# Principal_v1.net
KiCad netlist of a schematic drawn in Altium Designer
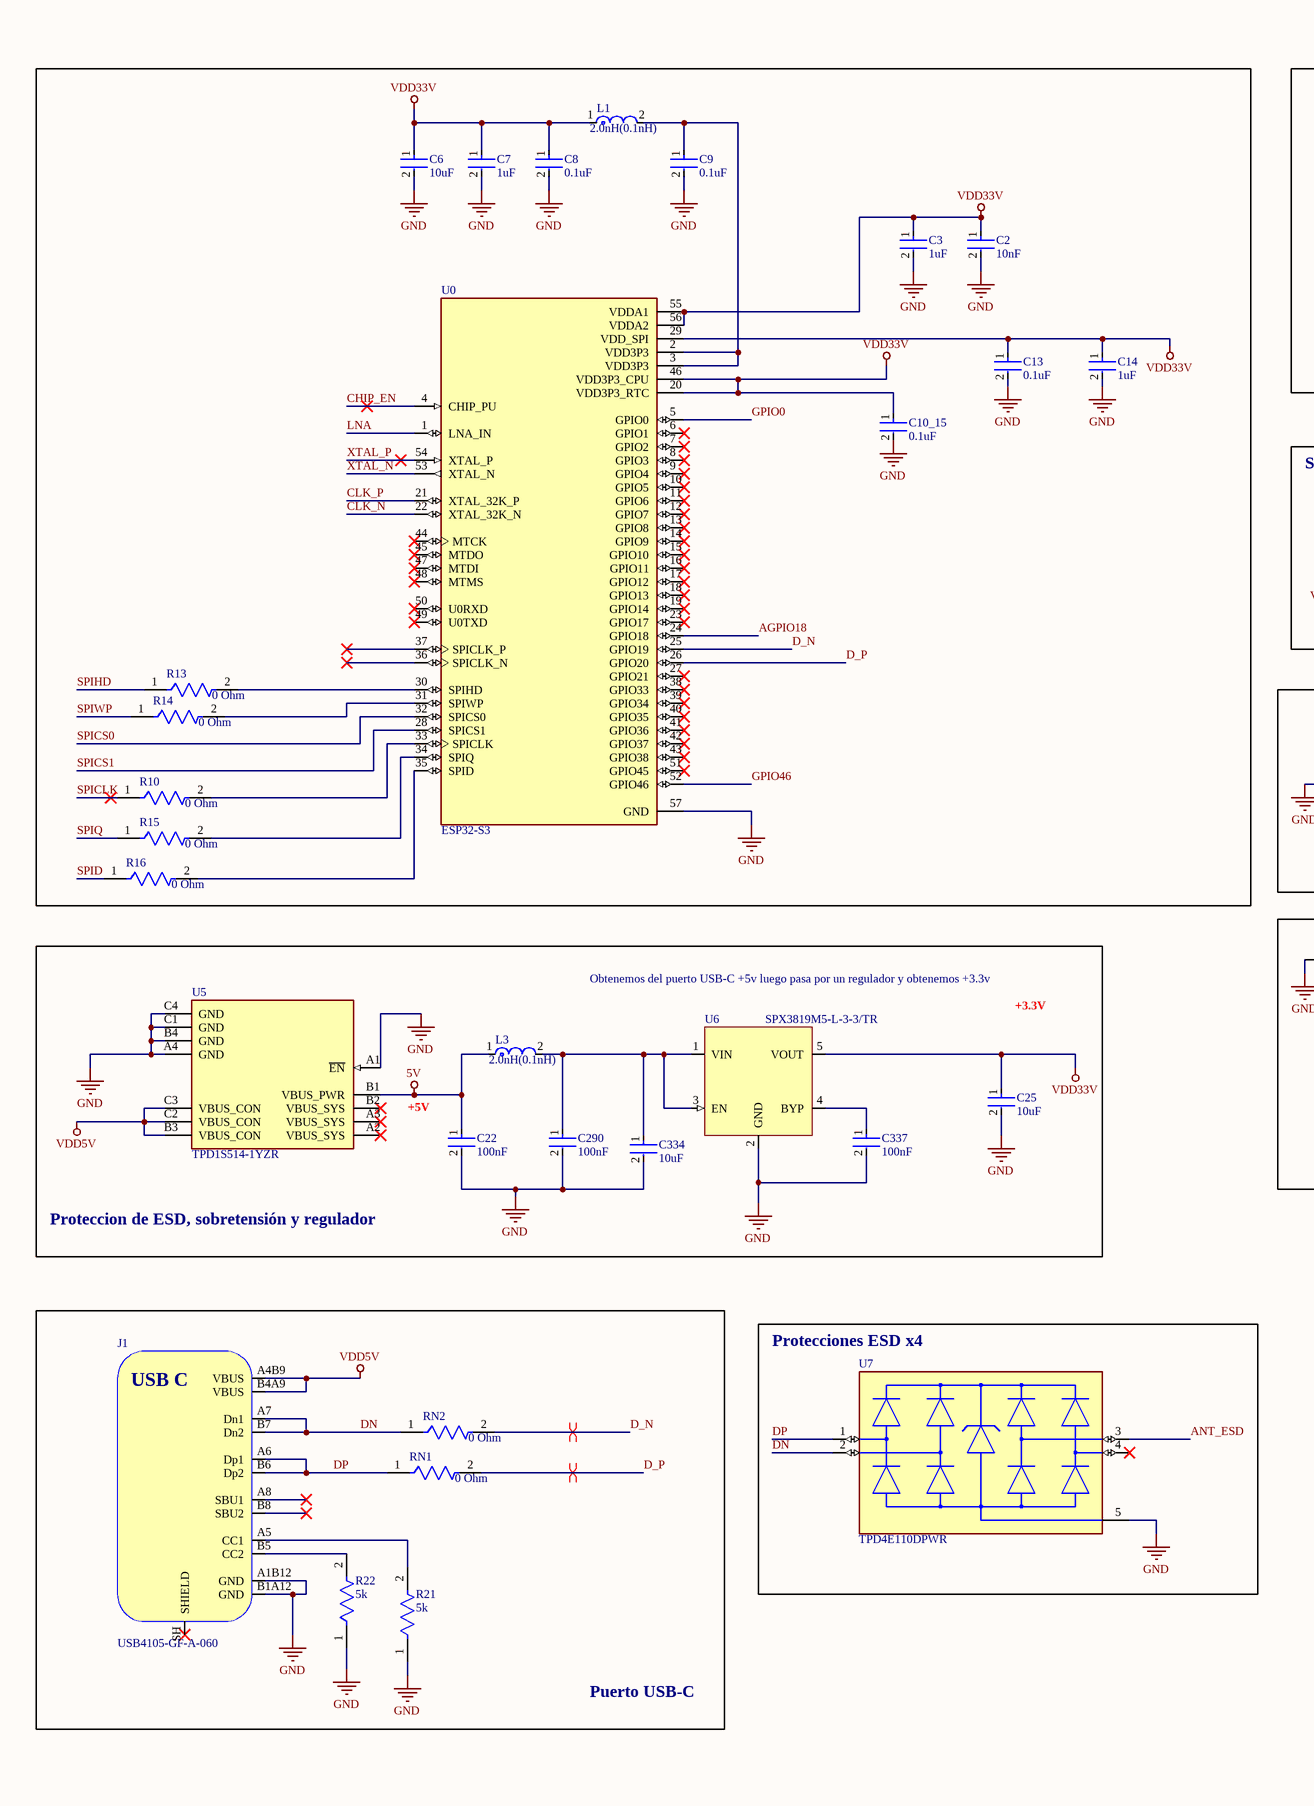
[diagram p0: Principal_v1.SchDoc, left]
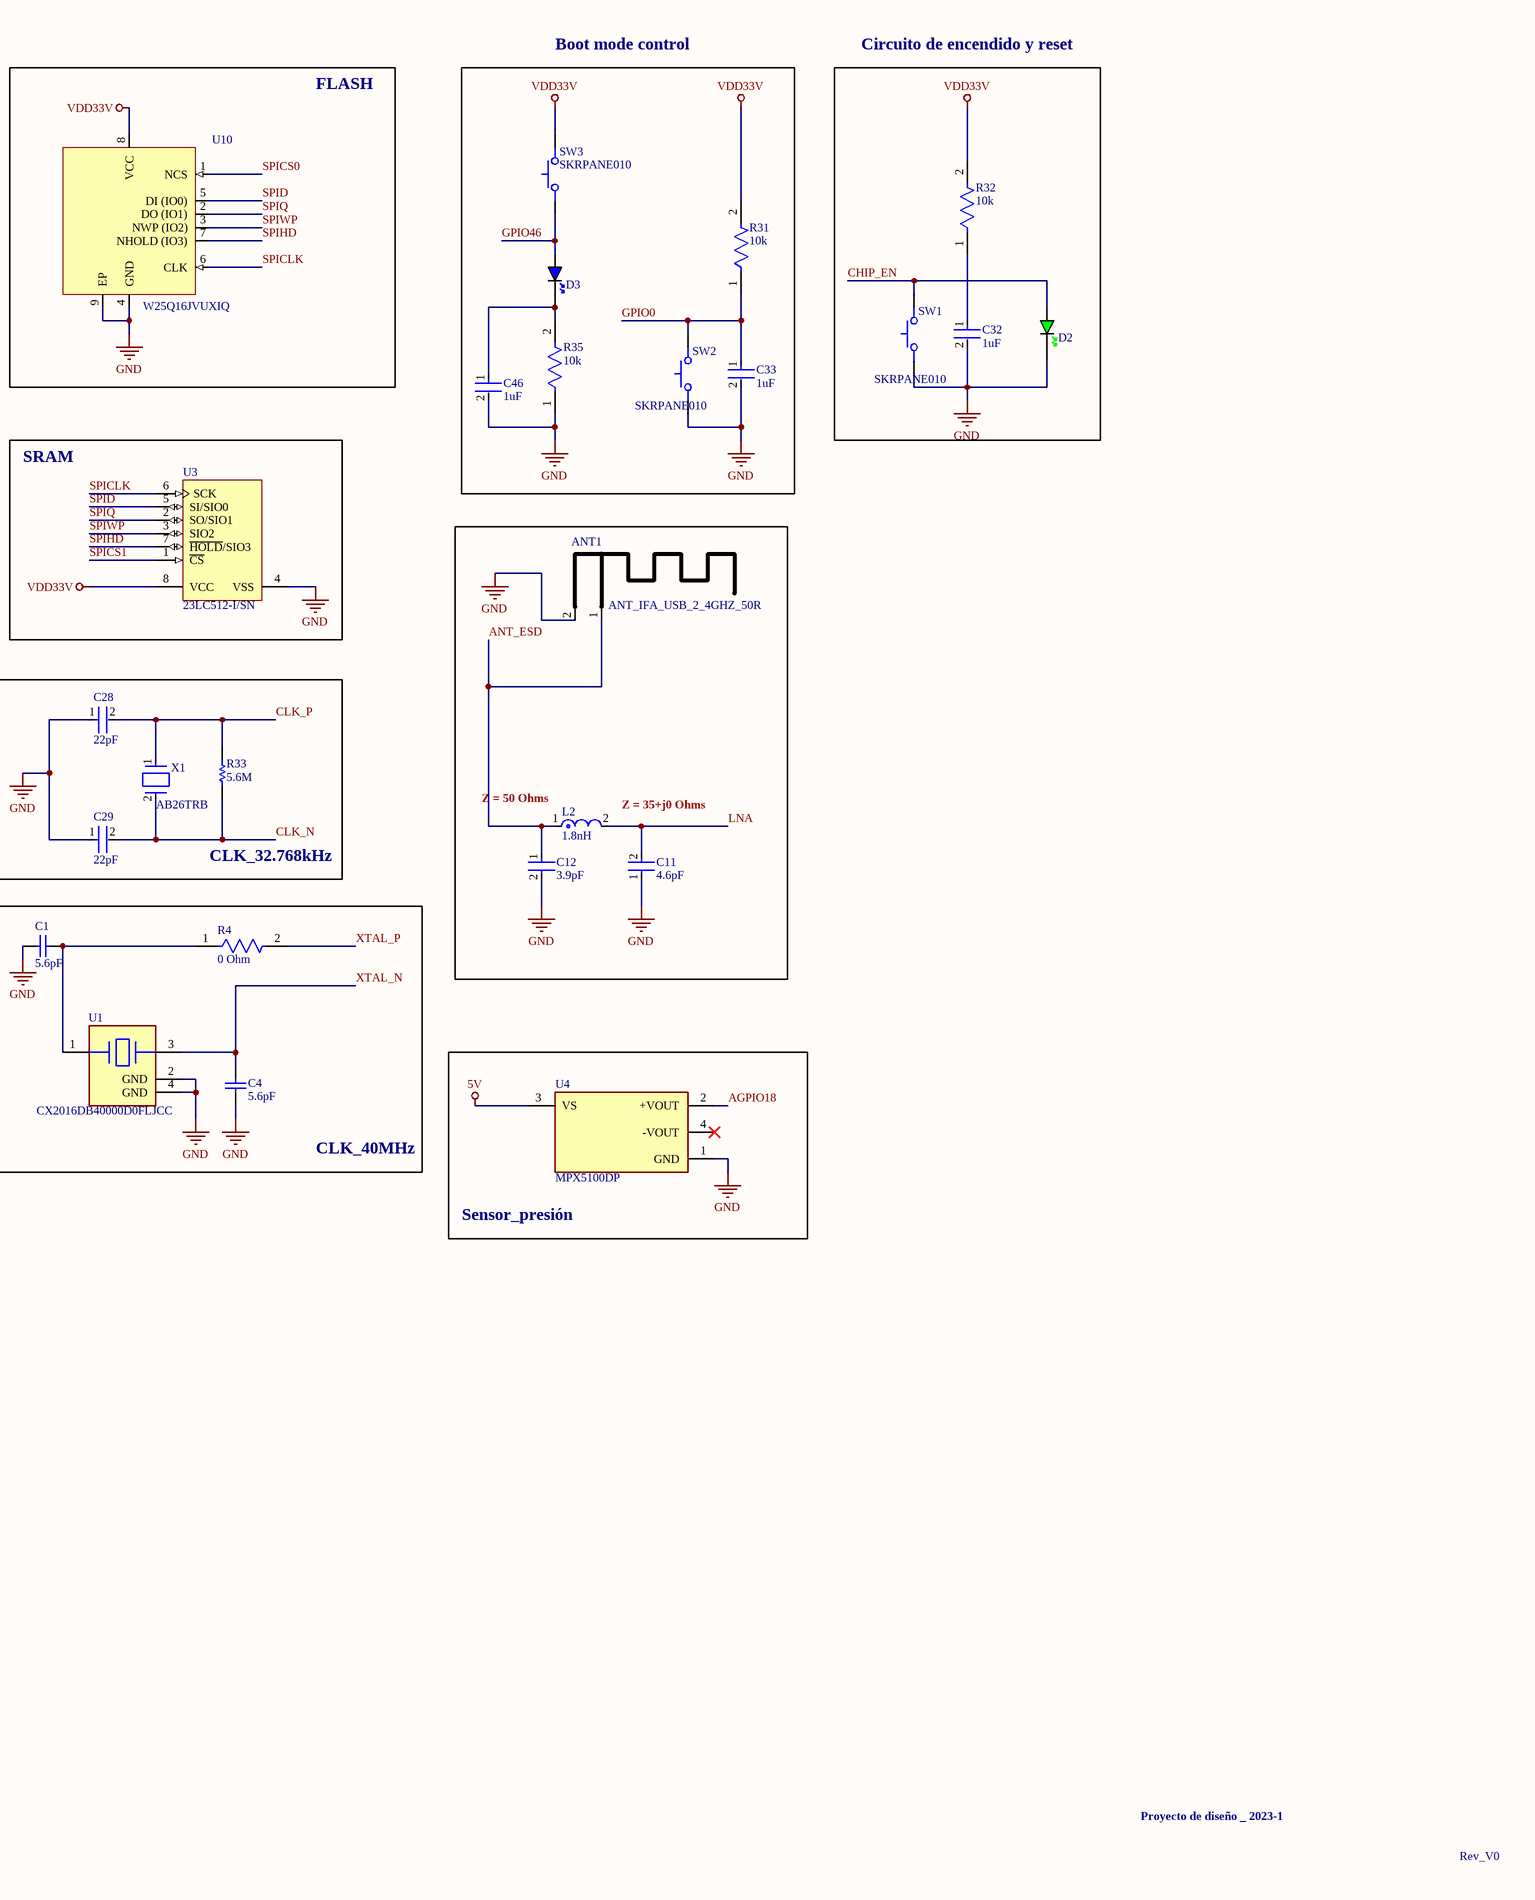
[diagram p1: Principal_v1.SchDoc, right]

(export (version "E")
  (design (tool "Eeschema 10.0.6"))
  (components
    (comp (ref "ANT1")
      (value "ANT_IFA_USB_2_4GHZ_50R")
      (footprint "ANT_IFA_USB_2_4GHZ_50R")
      (description "Inverted F 2.4GHz ISM PCB Antenna 50 Ohm")
      (fields (field (name "SOURCE") "Schematic-Lib-PhilsLab.SchLib"))
      (libsource (lib "Universidad Industrial de Santander") (part "ANT_IFA_USB_2_4GHZ_50R"))
    )
    (comp (ref "C1")
      (value "5.6pF")
      (footprint "CAPC1006X50X20LL10T10")
      (fields
        (field (name "MANUFACTURER") "AVX Interconnect / Elco")
        (field (name "PART NUMBER") "04023J5R6BBSTR")
      )
      (libsource (lib "Altium Content Vault") (part "CAP"))
    )
    (comp (ref "C2")
      (value "10nF")
      (footprint "FP-GRM033-0_03-IPC_B")
      (description "Chip Multilayer Ceramic Capacitors for General Purpose, 0201, 10000pF, X7R, 15%, 10%, 10V")
      (fields (field (name "VOLTAGE") "10V") (field (name "TOLERANCE") "10%"))
      (libsource (lib "Altium Content Vault") (part "b4654b650e69147ec39a6b967a45e02"))
    )
    (comp (ref "C3")
      (value "1uF")
      (footprint "FP-C0402C105K9PACTU-MFG")
      (description "CAP CER 1UF 6.3V X5R 0402")
      (fields (field (name "TOLERANCE") "10%") (field (name "VOLTAGE") "6.3V"))
      (libsource (lib "Altium Content Vault") (part "11868f565c42a9108669ba33697ecf6"))
    )
    (comp (ref "C4")
      (value "5.6pF")
      (footprint "CAPC1006X50X20LL10T10")
      (fields
        (field (name "MANUFACTURER") "AVX Interconnect / Elco")
        (field (name "PART NUMBER") "04023J5R6BBSTR")
      )
      (libsource (lib "Altium Content Vault") (part "CAP"))
    )
    (comp (ref "C6")
      (value "10uF")
      (footprint "FP-GRM155-0_2-IPC_C")
      (description "Chip Multilayer Ceramic Capacitors for General Purpose, 0402, 10uF, X5R, 15%, 20%, 6.3V")
      (libsource (lib "Altium Content Vault") (part "b4654b650e69147ec39a6b967a45e02"))
    )
    (comp (ref "C7")
      (value "1uF")
      (footprint "FP-C0402C105K9PACTU-MFG")
      (description "CAP CER 1UF 6.3V X5R 0402")
      (fields (field (name "TOLERANCE") "10%") (field (name "VOLTAGE") "6.3V"))
      (libsource (lib "Altium Content Vault") (part "11868f565c42a9108669ba33697ecf6"))
    )
    (comp (ref "C8")
      (value "0.1uF")
      (footprint "FP-CL278-IPC_C")
      (description "Cap Ceramic 100nF 25V X5R ±10% SMD 0402 +85°C Paper T/R")
      (fields (field (name "VOLTAGE") "25V") (field (name "TOLERANCE") "10%"))
      (libsource (lib "Altium Content Vault") (part "b4654b650e69147ec39a6b967a45e02"))
    )
    (comp (ref "C9")
      (value "0.1uF")
      (footprint "FP-CL278-IPC_C")
      (description "Cap Ceramic 100nF 25V X5R ±10% SMD 0402 +85°C Paper T/R")
      (fields (field (name "VOLTAGE") "25V") (field (name "TOLERANCE") "10%"))
      (libsource (lib "Altium Content Vault") (part "b4654b650e69147ec39a6b967a45e02"))
    )
    (comp (ref "C10_15")
      (value "0.1uF")
      (footprint "FP-CL278-IPC_C")
      (description "Cap Ceramic 100nF 25V X5R ±10% SMD 0402 +85°C Paper T/R")
      (fields (field (name "VOLTAGE") "25V") (field (name "TOLERANCE") "10%"))
      (libsource (lib "Altium Content Vault") (part "b4654b650e69147ec39a6b967a45e02"))
    )
    (comp (ref "C11")
      (value "4.6pF")
      (footprint "FP-CBR04C-MFG")
      (description "CBR0402 4.6 pF 30ppm/°C 0.1 pF C0G 50 V")
      (fields (field (name "MANUFACTURER PART NUMBER") "CBR04C469B5GAC") (field (name "TOLERANCE") "0.1 pF"))
      (libsource (lib "Altium Content Vault") (part "236180d848d6139a670b325ea6854c9"))
    )
    (comp (ref "C12")
      (value "3.9pF")
      (footprint "FP-GRM033-0_03-IPC_B")
      (description "Chip Multilayer Ceramic Capacitors for General Purpose, 0201, 3.9pF, C0G, 30ppm/°C, 0.25pF, 50V")
      (libsource (lib "Altium Content Vault") (part "b4654b650e69147ec39a6b967a45e02"))
    )
    (comp (ref "C13")
      (value "0.1uF")
      (footprint "FP-CL278-IPC_C")
      (description "Cap Ceramic 100nF 25V X5R ±10% SMD 0402 +85°C Paper T/R")
      (fields (field (name "VOLTAGE") "25V") (field (name "TOLERANCE") "10%"))
      (libsource (lib "Altium Content Vault") (part "b4654b650e69147ec39a6b967a45e02"))
    )
    (comp (ref "C14")
      (value "1uF")
      (footprint "FP-C0402C105K9PACTU-MFG")
      (description "CAP CER 1UF 6.3V X5R 0402")
      (fields (field (name "TOLERANCE") "10%") (field (name "VOLTAGE") "6.3V"))
      (libsource (lib "Altium Content Vault") (part "11868f565c42a9108669ba33697ecf6"))
    )
    (comp (ref "C22")
      (value "100nF")
      (footprint "FP-CL278-IPC_C")
      (description "Cap Ceramic 100nF 25V X5R ±10% SMD 0402 +85°C Paper T/R")
      (fields (field (name "VOLTAGE") "25V") (field (name "TOLERANCE") "10%"))
      (libsource (lib "Altium Content Vault") (part "b4654b650e69147ec39a6b967a45e02"))
    )
    (comp (ref "C25")
      (value "10uF")
      (footprint "FP-GRM155-0_2-IPC_C")
      (description "Chip Multilayer Ceramic Capacitors for General Purpose, 0402, 10uF, X5R, 15%, 20%, 6.3V")
      (libsource (lib "Altium Content Vault") (part "b4654b650e69147ec39a6b967a45e02"))
    )
    (comp (ref "C28")
      (value "22pF")
      (footprint "FP-C0603C-CF-MFG")
      (description "Cap Ceramic 22pF 50V C0G 5% SMD 0603 125°C Paper T/R")
      (fields (field (name "MANUFACTURER PART NUMBER") "C0603C220J5GACTU") (field (name "TOLERANCE") "0.05"))
      (libsource (lib "Altium Content Vault") (part "b4654b650e69147ec39a6b967a45e02"))
    )
    (comp (ref "C29")
      (value "22pF")
      (footprint "FP-C0603C-CF-MFG")
      (description "Cap Ceramic 22pF 50V C0G 5% SMD 0603 125°C Paper T/R")
      (fields (field (name "MANUFACTURER PART NUMBER") "C0603C220J5GACTU") (field (name "TOLERANCE") "0.05"))
      (libsource (lib "Altium Content Vault") (part "b4654b650e69147ec39a6b967a45e02"))
    )
    (comp (ref "C32")
      (value "1uF")
      (footprint "FP-C0402C105K9PACTU-MFG")
      (description "CAP CER 1UF 6.3V X5R 0402")
      (fields (field (name "TOLERANCE") "10%") (field (name "VOLTAGE") "6.3V"))
      (libsource (lib "Altium Content Vault") (part "11868f565c42a9108669ba33697ecf6"))
    )
    (comp (ref "C33")
      (value "1uF")
      (footprint "FP-C0402C105K9PACTU-MFG")
      (description "CAP CER 1UF 6.3V X5R 0402")
      (fields (field (name "TOLERANCE") "10%") (field (name "VOLTAGE") "6.3V"))
      (libsource (lib "Altium Content Vault") (part "11868f565c42a9108669ba33697ecf6"))
    )
    (comp (ref "C46")
      (value "1uF")
      (footprint "FP-C0402C105K9PACTU-MFG")
      (description "CAP CER 1UF 6.3V X5R 0402")
      (fields (field (name "TOLERANCE") "10%") (field (name "VOLTAGE") "6.3V"))
      (libsource (lib "Altium Content Vault") (part "11868f565c42a9108669ba33697ecf6"))
    )
    (comp (ref "C290")
      (value "100nF")
      (footprint "FP-CL278-IPC_C")
      (description "Cap Ceramic 100nF 25V X5R ±10% SMD 0402 +85°C Paper T/R")
      (fields (field (name "VOLTAGE") "25V") (field (name "TOLERANCE") "10%"))
      (libsource (lib "Altium Content Vault") (part "b4654b650e69147ec39a6b967a45e02"))
    )
    (comp (ref "C334")
      (value "10uF")
      (footprint "FP-GRM155-0_2-IPC_C")
      (description "Chip Multilayer Ceramic Capacitors for General Purpose, 0402, 10uF, X5R, 15%, 20%, 6.3V")
      (libsource (lib "Altium Content Vault") (part "b4654b650e69147ec39a6b967a45e02"))
    )
    (comp (ref "C337")
      (value "100nF")
      (footprint "FP-CL278-IPC_C")
      (description "Cap Ceramic 100nF 25V X5R ±10% SMD 0402 +85°C Paper T/R")
      (fields (field (name "VOLTAGE") "25V") (field (name "TOLERANCE") "10%"))
      (libsource (lib "Altium Content Vault") (part "b4654b650e69147ec39a6b967a45e02"))
    )
    (comp (ref "D2")
      (value "GREEN")
      (footprint "LED_0603_GREEN")
      (description "LED 0603 GREEN SMD")
      (libsource (lib "Schematic-Lib-PhilsLab") (part "LED_0603_GREEN"))
    )
    (comp (ref "D3")
      (value "BLUE")
      (footprint "LED_0603_BLUE")
      (description "LED 0603 BLUE SMD")
      (libsource (lib "Schematic-Lib-PhilsLab") (part "LED_0603_BLUE"))
    )
    (comp (ref "J1")
      (value "USB4105-GF-A-060")
      (footprint "USB4105-GF-A-060")
      (description "USB Connector Type C SMT 12 Pin")
      (fields (field (name "MANUFACTURER") "GCT") (field (name "SOURCE") "Schematic-Lib-PhilsLab.SchLib"))
      (libsource (lib "Universidad Industrial de Santander") (part "USB4105-GF-A-060"))
    )
    (comp (ref "L1")
      (value "2.0nH(0.1nH)")
      (footprint "FP-LQG15HH_02-MFG")
      (description "Multilayer type RF Inductor 2nH ±0.1nH 0.09Ω 900mA 0402")
      (libsource (lib "Altium Content Vault") (part "4cc4b267dca4c8e51f7102f422741d8"))
    )
    (comp (ref "L2")
      (value "1.8nH")
      (footprint "FP-LQP03TG_02-IPC_B")
      (description "Film type RF Inductor 1.8nH ±0.1nH 600mA 0.15Ω 0201 (0603)")
      (libsource (lib "Altium Content Vault") (part "4cc4b267dca4c8e51f7102f422741d8"))
    )
    (comp (ref "L3")
      (value "2.0nH(0.1nH)")
      (footprint "FP-LQG15HH_02-MFG")
      (description "Multilayer type RF Inductor 2nH ±0.1nH 0.09Ω 900mA 0402")
      (libsource (lib "Altium Content Vault") (part "4cc4b267dca4c8e51f7102f422741d8"))
    )
    (comp (ref "R4")
      (value "0 Ohm")
      (footprint "FP-RMCF0402-MFG")
      (description "RES 0 OHM JUMPER 1/16W 0402")
      (libsource (lib "Altium Content Vault") (part "1029c3af85768c4190bb7ad29bc67b5"))
    )
    (comp (ref "R10")
      (value "0 Ohm")
      (footprint "FP-RMCF0402-MFG")
      (description "RES 0 OHM JUMPER 1/16W 0402")
      (libsource (lib "Altium Content Vault") (part "1029c3af85768c4190bb7ad29bc67b5"))
    )
    (comp (ref "R13")
      (value "0 Ohm")
      (footprint "FP-RMCF0402-MFG")
      (description "RES 0 OHM JUMPER 1/16W 0402")
      (libsource (lib "Altium Content Vault") (part "1029c3af85768c4190bb7ad29bc67b5"))
    )
    (comp (ref "R14")
      (value "0 Ohm")
      (footprint "FP-RMCF0402-MFG")
      (description "RES 0 OHM JUMPER 1/16W 0402")
      (libsource (lib "Altium Content Vault") (part "1029c3af85768c4190bb7ad29bc67b5"))
    )
    (comp (ref "R15")
      (value "0 Ohm")
      (footprint "FP-RMCF0402-MFG")
      (description "RES 0 OHM JUMPER 1/16W 0402")
      (libsource (lib "Altium Content Vault") (part "1029c3af85768c4190bb7ad29bc67b5"))
    )
    (comp (ref "R16")
      (value "0 Ohm")
      (footprint "FP-RMCF0402-MFG")
      (description "RES 0 OHM JUMPER 1/16W 0402")
      (libsource (lib "Altium Content Vault") (part "1029c3af85768c4190bb7ad29bc67b5"))
    )
    (comp (ref "R21")
      (value "5k")
      (footprint "FP-PNM0402-IPC_C")
      (description "RES SMD 5K OHM 0.1% 1/20W 0402")
      (fields (field (name "TOLERANCE") "0.1%"))
      (libsource (lib "Altium Content Vault") (part "1029c3af85768c4190bb7ad29bc67b5"))
    )
    (comp (ref "R22")
      (value "5k")
      (footprint "FP-PNM0402-IPC_C")
      (description "RES SMD 5K OHM 0.1% 1/20W 0402")
      (fields (field (name "TOLERANCE") "0.1%"))
      (libsource (lib "Altium Content Vault") (part "1029c3af85768c4190bb7ad29bc67b5"))
    )
    (comp (ref "R31")
      (value "10k")
      (footprint "FP-CRGP0603-IPC_C")
      (description "CRGP 0603 10K 1%")
      (fields
        (field (name "OCTOPART") "https://octopart.com/crgp0603f10k-te+connectivity-91018721")
        (field (name "MANUFACTURER PART NUMBER") "CRGP0603F10K")
      )
      (libsource (lib "Altium Content Vault") (part "1029c3af85768c4190bb7ad29bc67b5"))
    )
    (comp (ref "R32")
      (value "10k")
      (footprint "FP-CRGP0603-IPC_C")
      (description "CRGP 0603 10K 1%")
      (fields
        (field (name "OCTOPART") "https://octopart.com/crgp0603f10k-te+connectivity-91018721")
        (field (name "MANUFACTURER PART NUMBER") "CRGP0603F10K")
      )
      (libsource (lib "Altium Content Vault") (part "1029c3af85768c4190bb7ad29bc67b5"))
    )
    (comp (ref "R33")
      (value "5.6M")
      (footprint "RESC1005X40X25ML05T10")
      (fields (field (name "MANUFACTURER") "Yageo / Phycomp") (field (name "PART NUMBER") "RC0402JR-075M6L"))
      (libsource (lib "Altium Content Vault") (part "RES"))
    )
    (comp (ref "R35")
      (value "10k")
      (footprint "FP-CRGP0603-IPC_C")
      (description "CRGP 0603 10K 1%")
      (fields
        (field (name "OCTOPART") "https://octopart.com/crgp0603f10k-te+connectivity-91018721")
        (field (name "MANUFACTURER PART NUMBER") "CRGP0603F10K")
      )
      (libsource (lib "Altium Content Vault") (part "1029c3af85768c4190bb7ad29bc67b5"))
    )
    (comp (ref "RN1")
      (value "0 Ohm")
      (footprint "FP-RMCF0402-MFG")
      (description "RES 0 OHM JUMPER 1/16W 0402")
      (libsource (lib "Altium Content Vault") (part "1029c3af85768c4190bb7ad29bc67b5"))
    )
    (comp (ref "RN2")
      (value "0 Ohm")
      (footprint "FP-RMCF0402-MFG")
      (description "RES 0 OHM JUMPER 1/16W 0402")
      (libsource (lib "Altium Content Vault") (part "1029c3af85768c4190bb7ad29bc67b5"))
    )
    (comp (ref "SW1")
      (value "SKRPANE010")
      (footprint "SKRPANE010")
      (description "Tactile Switch SMD SPST")
      (fields (field (name "MANUFACTURER") "Alps Alpine"))
      (libsource (lib "Schematic-Lib-PhilsLab") (part "SKRPANE010"))
    )
    (comp (ref "SW2")
      (value "SKRPANE010")
      (footprint "SKRPANE010")
      (description "Tactile Switch SMD SPST")
      (fields (field (name "MANUFACTURER") "Alps Alpine"))
      (libsource (lib "Schematic-Lib-PhilsLab") (part "SKRPANE010"))
    )
    (comp (ref "SW3")
      (value "SKRPANE010")
      (footprint "SKRPANE010")
      (description "Tactile Switch SMD SPST")
      (fields (field (name "MANUFACTURER") "Alps Alpine"))
      (libsource (lib "Schematic-Lib-PhilsLab") (part "SKRPANE010"))
    )
    (comp (ref "U0")
      (value "ESP32-S3")
      (footprint "IC_ESP32-S3")
      (fields (field (name "MF") "Espressif Systems"))
      (libsource (lib "Universidad Industrial de Santander") (part "ESP32-S3"))
    )
    (comp (ref "U1")
      (value "CX2016DB40000D0FLJCC")
      (footprint "FP-CX2016DB-MFG")
      (description "CRYSTAL 40.0000MHZ 8PF SMD")
      (fields
        (field (name "TOLERANCE") "15ppm")
        (field (name "OCTOPART") "https://octopart.com/cx2016db40000d0fljcc-avx+%2F+kyocera-71139660")
      )
      (libsource (lib "Altium Content Vault") (part "28df8d7a1f20b35eca55ec9e48b468b"))
    )
    (comp (ref "U3")
      (value "23LC512-I/SN")
      (footprint "MCHP-SOIC-SN8_N")
      (fields (field (name "MANUFACTURER") "Microchip"))
      (libsource (lib "Altium Content Vault") (part "MCHP-23A1024_512-LC1024_512-8"))
    )
    (comp (ref "U4")
      (value "MPX5100DP")
      (footprint "FP-SOT1754-1-MFG")
      (libsource (lib "Altium Content Vault") (part "60e7d013c733a87ffd9e1aafd0260a2"))
    )
    (comp (ref "U5")
      (value "TPD1S514-1YZR")
      (footprint "BGA12N40P3X4_140X189X62N")
      (description "Interface Circuit, PBGA12")
      (fields (field (name "MF") "Texas Instruments"))
      (libsource (lib "Universidad Industrial de Santander") (part "TPD1S514-1YZR"))
    )
    (comp (ref "U6")
      (value "SPX3819M5-L-3-3/TR")
      (footprint "SOT-23-5")
      (description "500mA +3.3V Low-Noise LDO Voltage Regulator")
      (fields
        (field (name "MANUFACTURER") "MaxLinear")
        (field (name "SOURCE") "Schematic-Lib-PhilsLab.SchLib")
      )
      (libsource (lib "Universidad Industrial de Santander") (part "SPX3819M5-L-3-3/TR"))
    )
    (comp (ref "U7")
      (value "TPD4E110DPWR")
      (footprint "FP-DPW0004A-MFG")
      (description "TVS DIODE 5.5VWM 13VC 4X2SON")
      (libsource (lib "Altium Content Vault") (part "dc33b8a9bfad9debc17581ebbb18bcc"))
    )
    (comp (ref "U10")
      (value "W25Q16JVUXIQ")
      (footprint "USON-8-2X3MM")
      (description "16M-BIT SERIAL FLASH MEMORY WITH DUAL/QUAD SPI USON-8")
      (fields (field (name "MANUFACTURER") "Winbond") (field (name "SOURCE") "Schematic-Lib-PhilsLab.SchLib"))
      (libsource (lib "Universidad Industrial de Santander") (part "W25Q16JVUXIQ"))
    )
    (comp (ref "X1")
      (value "AB26TRB")
      (footprint "FP-AB26TRB-MFG")
      (description "CRYSTAL 32.7680KHZ 12.5PF TH")
      (fields (field (name "TOLERANCE") "20ppm"))
      (libsource (lib "Altium Content Vault") (part "c23a69dc6c9e2f18f2079038eb95dd1"))
    )
  )
  (nets
    (net (code "1") (name "/AGPIO18") (class "Default")
      (node (ref "U0") (pin "24") (pinfunction "GPIO18_24") (pintype "bidirectional"))
      (node (ref "U4") (pin "2") (pinfunction "+VOUT_2") (pintype "passive"))
    )
    (net (code "2") (name "/ANT_ESD") (class "Default")
      (node (ref "ANT1") (pin "1") (pinfunction "RF_1") (pintype "passive"))
      (node (ref "C12") (pin "1") (pinfunction "1_1") (pintype "passive"))
      (node (ref "L2") (pin "1") (pinfunction "1_1") (pintype "passive"))
      (node (ref "U7") (pin "3") (pinfunction "IO3_3") (pintype "bidirectional"))
    )
    (net (code "3") (name "/CHIP_EN") (class "Default")
      (node (ref "D2") (pin "A") (pinfunction "A_A") (pintype "passive"))
      (node (ref "SW1") (pin "34") (pintype "passive"))
      (node (ref "U0") (pin "4") (pinfunction "CHIP_PU_4") (pintype "input"))
    )
    (net (code "4") (name "/CLK_N") (class "Default")
      (node (ref "C29") (pin "2") (pinfunction "2_2") (pintype "passive"))
      (node (ref "R33") (pin "1") (pinfunction "1_1") (pintype "passive"))
      (node (ref "U0") (pin "22") (pinfunction "XTAL_32K_N_22") (pintype "bidirectional"))
      (node (ref "X1") (pin "2") (pinfunction "2_2") (pintype "passive"))
    )
    (net (code "5") (name "/CLK_P") (class "Default")
      (node (ref "C28") (pin "2") (pinfunction "2_2") (pintype "passive"))
      (node (ref "R33") (pin "2") (pinfunction "2_2") (pintype "passive"))
      (node (ref "U0") (pin "21") (pinfunction "XTAL_32K_P_21") (pintype "bidirectional"))
      (node (ref "X1") (pin "1") (pinfunction "1_1") (pintype "passive"))
    )
    (net (code "6") (name "/DN") (class "Default")
      (node (ref "J1") (pin "A7") (pinfunction "Dn1_A7") (pintype "passive"))
      (node (ref "J1") (pin "B7") (pinfunction "Dn2_B7") (pintype "passive"))
      (node (ref "RN2") (pin "1") (pinfunction "1_1") (pintype "passive"))
      (node (ref "U7") (pin "2") (pinfunction "IO2_2") (pintype "bidirectional"))
    )
    (net (code "7") (name "/DP") (class "Default")
      (node (ref "J1") (pin "A6") (pinfunction "Dp1_A6") (pintype "passive"))
      (node (ref "J1") (pin "B6") (pinfunction "Dp2_B6") (pintype "passive"))
      (node (ref "RN1") (pin "1") (pinfunction "1_1") (pintype "passive"))
      (node (ref "U7") (pin "1") (pinfunction "IO1_1") (pintype "bidirectional"))
    )
    (net (code "8") (name "/D_N") (class "Default")
      (node (ref "RN2") (pin "2") (pinfunction "2_2") (pintype "passive"))
      (node (ref "U0") (pin "25") (pinfunction "GPIO19_25") (pintype "bidirectional"))
    )
    (net (code "9") (name "/D_P") (class "Default")
      (node (ref "RN1") (pin "2") (pinfunction "2_2") (pintype "passive"))
      (node (ref "U0") (pin "26") (pinfunction "GPIO20_26") (pintype "bidirectional"))
    )
    (net (code "10") (name "/GPIO0") (class "Default")
      (node (ref "C33") (pin "1") (pinfunction "1_1") (pintype "passive"))
      (node (ref "R31") (pin "1") (pinfunction "1_1") (pintype "passive"))
      (node (ref "SW2") (pin "34") (pintype "passive"))
      (node (ref "U0") (pin "5") (pinfunction "GPIO0_5") (pintype "bidirectional"))
    )
    (net (code "11") (name "/GPIO46") (class "Default")
      (node (ref "D3") (pin "A") (pinfunction "A_A") (pintype "passive"))
      (node (ref "SW3") (pin "12") (pintype "passive"))
      (node (ref "U0") (pin "52") (pinfunction "GPIO46_52") (pintype "bidirectional"))
    )
    (net (code "12") (name "/LNA") (class "Default")
      (node (ref "C11") (pin "2") (pinfunction "2_2") (pintype "passive"))
      (node (ref "L2") (pin "2") (pinfunction "2_2") (pintype "passive"))
      (node (ref "U0") (pin "1") (pinfunction "LNA_IN_1") (pintype "bidirectional"))
    )
    (net (code "13") (name "/SPICLK") (class "Default")
      (node (ref "R10") (pin "1") (pinfunction "1_1") (pintype "passive"))
      (node (ref "U10") (pin "6") (pinfunction "CLK_6") (pintype "input"))
      (node (ref "U3") (pin "6") (pinfunction "SCK_6") (pintype "input"))
    )
    (net (code "14") (name "/SPICS0") (class "Default")
      (node (ref "U0") (pin "32") (pinfunction "SPICS0_32") (pintype "bidirectional"))
      (node (ref "U10") (pin "1") (pinfunction "NCS_1") (pintype "input"))
    )
    (net (code "15") (name "/SPICS1") (class "Default")
      (node (ref "U0") (pin "28") (pinfunction "SPICS1_28") (pintype "bidirectional"))
      (node (ref "U3") (pin "1") (pinfunction "~{CS}_1") (pintype "input"))
    )
    (net (code "16") (name "/SPID") (class "Default")
      (node (ref "R16") (pin "1") (pinfunction "1_1") (pintype "passive"))
      (node (ref "U10") (pin "5") (pinfunction "DI_(IO0)_5") (pintype "bidirectional"))
      (node (ref "U3") (pin "5") (pinfunction "SI/SIO0_5") (pintype "bidirectional"))
    )
    (net (code "17") (name "/SPIHD") (class "Default")
      (node (ref "R13") (pin "1") (pinfunction "1_1") (pintype "passive"))
      (node (ref "U10") (pin "7") (pinfunction "NHOLD_(IO3)_7") (pintype "bidirectional"))
      (node (ref "U3") (pin "7") (pinfunction "~{HOLD}/SIO3_7") (pintype "bidirectional"))
    )
    (net (code "18") (name "/SPIQ") (class "Default")
      (node (ref "R15") (pin "1") (pinfunction "1_1") (pintype "passive"))
      (node (ref "U10") (pin "2") (pinfunction "DO_(IO1)_2") (pintype "bidirectional"))
      (node (ref "U3") (pin "2") (pinfunction "SO/SIO1_2") (pintype "bidirectional"))
    )
    (net (code "19") (name "/SPIWP") (class "Default")
      (node (ref "R14") (pin "1") (pinfunction "1_1") (pintype "passive"))
      (node (ref "U10") (pin "3") (pinfunction "NWP_(IO2)_3") (pintype "bidirectional"))
      (node (ref "U3") (pin "3") (pinfunction "SIO2_3") (pintype "bidirectional"))
    )
    (net (code "20") (name "/XTAL_N") (class "Default")
      (node (ref "C4") (pin "2") (pinfunction "2_2") (pintype "passive"))
      (node (ref "U0") (pin "53") (pinfunction "XTAL_N_53") (pintype "output"))
      (node (ref "U1") (pin "3") (pinfunction "3_3") (pintype "passive"))
    )
    (net (code "21") (name "/XTAL_P") (class "Default")
      (node (ref "R4") (pin "2") (pinfunction "2_2") (pintype "passive"))
      (node (ref "U0") (pin "54") (pinfunction "XTAL_P_54") (pintype "input"))
    )
    (net (code "22") (name "5V") (class "Default")
      (node (ref "C22") (pin "1") (pinfunction "1_1") (pintype "passive"))
      (node (ref "L3") (pin "1") (pinfunction "1_1") (pintype "passive"))
      (node (ref "U4") (pin "3") (pinfunction "VS_3") (pintype "power_in"))
      (node (ref "U5") (pin "B1") (pinfunction "VBUS_PWR_B1") (pintype "power_in"))
    )
    (net (code "23") (name "GND") (class "Default")
      (node (ref "ANT1") (pin "2") (pinfunction "GND_2") (pintype "passive"))
      (node (ref "C1") (pin "1") (pinfunction "1_1") (pintype "passive"))
      (node (ref "C10_15") (pin "2") (pinfunction "2_2") (pintype "passive"))
      (node (ref "C11") (pin "1") (pinfunction "1_1") (pintype "passive"))
      (node (ref "C12") (pin "2") (pinfunction "2_2") (pintype "passive"))
      (node (ref "C13") (pin "2") (pinfunction "2_2") (pintype "passive"))
      (node (ref "C14") (pin "2") (pinfunction "2_2") (pintype "passive"))
      (node (ref "C2") (pin "2") (pinfunction "2_2") (pintype "passive"))
      (node (ref "C22") (pin "2") (pinfunction "2_2") (pintype "passive"))
      (node (ref "C25") (pin "2") (pinfunction "2_2") (pintype "passive"))
      (node (ref "C28") (pin "1") (pinfunction "1_1") (pintype "passive"))
      (node (ref "C29") (pin "1") (pinfunction "1_1") (pintype "passive"))
      (node (ref "C290") (pin "2") (pinfunction "2_2") (pintype "passive"))
      (node (ref "C3") (pin "2") (pinfunction "2_2") (pintype "passive"))
      (node (ref "C32") (pin "2") (pinfunction "2_2") (pintype "passive"))
      (node (ref "C33") (pin "2") (pinfunction "2_2") (pintype "passive"))
      (node (ref "C334") (pin "2") (pinfunction "2_2") (pintype "passive"))
      (node (ref "C337") (pin "2") (pinfunction "2_2") (pintype "passive"))
      (node (ref "C4") (pin "1") (pinfunction "1_1") (pintype "passive"))
      (node (ref "C46") (pin "2") (pinfunction "2_2") (pintype "passive"))
      (node (ref "C6") (pin "2") (pinfunction "2_2") (pintype "passive"))
      (node (ref "C7") (pin "2") (pinfunction "2_2") (pintype "passive"))
      (node (ref "C8") (pin "2") (pinfunction "2_2") (pintype "passive"))
      (node (ref "C9") (pin "2") (pinfunction "2_2") (pintype "passive"))
      (node (ref "D2") (pin "K") (pinfunction "K_K") (pintype "passive"))
      (node (ref "J1") (pin "A1B12") (pinfunction "GND_A1B12") (pintype "passive"))
      (node (ref "J1") (pin "B1A12") (pinfunction "GND_B1A12") (pintype "passive"))
      (node (ref "R21") (pin "1") (pinfunction "1_1") (pintype "passive"))
      (node (ref "R22") (pin "1") (pinfunction "1_1") (pintype "passive"))
      (node (ref "R35") (pin "1") (pinfunction "1_1") (pintype "passive"))
      (node (ref "SW1") (pin "12") (pintype "passive"))
      (node (ref "SW2") (pin "12") (pintype "passive"))
      (node (ref "U0") (pin "57") (pinfunction "GND_57") (pintype "power_in"))
      (node (ref "U1") (pin "2") (pinfunction "GND_2") (pintype "power_in"))
      (node (ref "U1") (pin "4") (pinfunction "GND_4") (pintype "power_in"))
      (node (ref "U10") (pin "4") (pinfunction "GND_4") (pintype "power_in"))
      (node (ref "U10") (pin "9") (pinfunction "EP_9") (pintype "power_in"))
      (node (ref "U3") (pin "4") (pinfunction "VSS_4") (pintype "power_in"))
      (node (ref "U4") (pin "1") (pinfunction "GND_1") (pintype "power_in"))
      (node (ref "U5") (pin "A1") (pinfunction "~{EN}_A1") (pintype "input"))
      (node (ref "U5") (pin "A4") (pinfunction "GND_A4") (pintype "power_in"))
      (node (ref "U5") (pin "B4") (pinfunction "GND_B4") (pintype "power_in"))
      (node (ref "U5") (pin "C1") (pinfunction "GND_C1") (pintype "power_in"))
      (node (ref "U5") (pin "C4") (pinfunction "GND_C4") (pintype "power_in"))
      (node (ref "U6") (pin "2") (pinfunction "GND_2") (pintype "power_in"))
      (node (ref "U7") (pin "5") (pinfunction "GND_5") (pintype "power_in"))
    )
    (net (code "24") (name "Net-(C1-Pad2)") (class "Default")
      (node (ref "C1") (pin "2") (pinfunction "2_2") (pintype "passive"))
      (node (ref "R4") (pin "1") (pinfunction "1_1") (pintype "passive"))
      (node (ref "U1") (pin "1") (pinfunction "1_1") (pintype "passive"))
    )
    (net (code "25") (name "Net-(C9-Pad1)") (class "Default")
      (node (ref "C9") (pin "1") (pinfunction "1_1") (pintype "passive"))
      (node (ref "L1") (pin "2") (pinfunction "2_2") (pintype "passive"))
      (node (ref "U0") (pin "2") (pinfunction "VDD3P3_2") (pintype "power_in"))
      (node (ref "U0") (pin "3") (pinfunction "VDD3P3_3") (pintype "power_in"))
    )
    (net (code "26") (name "Net-(C32-Pad1)") (class "Default")
      (node (ref "C32") (pin "1") (pinfunction "1_1") (pintype "passive"))
      (node (ref "R32") (pin "1") (pinfunction "1_1") (pintype "passive"))
    )
    (net (code "27") (name "Net-(C46-Pad1)") (class "Default")
      (node (ref "C46") (pin "1") (pinfunction "1_1") (pintype "passive"))
      (node (ref "D3") (pin "K") (pinfunction "K_K") (pintype "passive"))
      (node (ref "R35") (pin "2") (pinfunction "2_2") (pintype "passive"))
    )
    (net (code "28") (name "Net-(J1-CC1)") (class "Default")
      (node (ref "J1") (pin "A5") (pinfunction "CC1_A5") (pintype "passive"))
      (node (ref "R21") (pin "2") (pinfunction "2_2") (pintype "passive"))
    )
    (net (code "29") (name "Net-(J1-CC2)") (class "Default")
      (node (ref "J1") (pin "B5") (pinfunction "CC2_B5") (pintype "passive"))
      (node (ref "R22") (pin "2") (pinfunction "2_2") (pintype "passive"))
    )
    (net (code "30") (name "Net-(U0-SPICLK)") (class "Default")
      (node (ref "R10") (pin "2") (pinfunction "2_2") (pintype "passive"))
      (node (ref "U0") (pin "33") (pinfunction "SPICLK_33") (pintype "bidirectional"))
    )
    (net (code "31") (name "Net-(U0-SPID)") (class "Default")
      (node (ref "R16") (pin "2") (pinfunction "2_2") (pintype "passive"))
      (node (ref "U0") (pin "35") (pinfunction "SPID_35") (pintype "bidirectional"))
    )
    (net (code "32") (name "Net-(U0-SPIHD)") (class "Default")
      (node (ref "R13") (pin "2") (pinfunction "2_2") (pintype "passive"))
      (node (ref "U0") (pin "30") (pinfunction "SPIHD_30") (pintype "bidirectional"))
    )
    (net (code "33") (name "Net-(U0-SPIQ)") (class "Default")
      (node (ref "R15") (pin "2") (pinfunction "2_2") (pintype "passive"))
      (node (ref "U0") (pin "34") (pinfunction "SPIQ_34") (pintype "bidirectional"))
    )
    (net (code "34") (name "Net-(U0-SPIWP)") (class "Default")
      (node (ref "R14") (pin "2") (pinfunction "2_2") (pintype "passive"))
      (node (ref "U0") (pin "31") (pinfunction "SPIWP_31") (pintype "bidirectional"))
    )
    (net (code "35") (name "Net-(U6-BYP)") (class "Default")
      (node (ref "C337") (pin "1") (pinfunction "1_1") (pintype "passive"))
      (node (ref "U6") (pin "4") (pinfunction "BYP_4") (pintype "passive"))
    )
    (net (code "36") (name "Net-(U6-EN)") (class "Default")
      (node (ref "C290") (pin "1") (pinfunction "1_1") (pintype "passive"))
      (node (ref "C334") (pin "1") (pinfunction "1_1") (pintype "passive"))
      (node (ref "L3") (pin "2") (pinfunction "2_2") (pintype "passive"))
      (node (ref "U6") (pin "1") (pinfunction "VIN_1") (pintype "power_in"))
      (node (ref "U6") (pin "3") (pinfunction "EN_3") (pintype "input"))
    )
    (net (code "37") (name "VDD5V") (class "Default")
      (node (ref "J1") (pin "A4B9") (pinfunction "VBUS_A4B9") (pintype "passive"))
      (node (ref "J1") (pin "B4A9") (pinfunction "VBUS_B4A9") (pintype "passive"))
      (node (ref "U5") (pin "B3") (pinfunction "VBUS_CON_B3") (pintype "power_in"))
      (node (ref "U5") (pin "C2") (pinfunction "VBUS_CON_C2") (pintype "power_in"))
      (node (ref "U5") (pin "C3") (pinfunction "VBUS_CON_C3") (pintype "power_in"))
    )
    (net (code "38") (name "VDD33V") (class "Default")
      (node (ref "C10_15") (pin "1") (pinfunction "1_1") (pintype "passive"))
      (node (ref "C13") (pin "1") (pinfunction "1_1") (pintype "passive"))
      (node (ref "C14") (pin "1") (pinfunction "1_1") (pintype "passive"))
      (node (ref "C2") (pin "1") (pinfunction "1_1") (pintype "passive"))
      (node (ref "C25") (pin "1") (pinfunction "1_1") (pintype "passive"))
      (node (ref "C3") (pin "1") (pinfunction "1_1") (pintype "passive"))
      (node (ref "C6") (pin "1") (pinfunction "1_1") (pintype "passive"))
      (node (ref "C7") (pin "1") (pinfunction "1_1") (pintype "passive"))
      (node (ref "C8") (pin "1") (pinfunction "1_1") (pintype "passive"))
      (node (ref "L1") (pin "1") (pinfunction "1_1") (pintype "passive"))
      (node (ref "R31") (pin "2") (pinfunction "2_2") (pintype "passive"))
      (node (ref "R32") (pin "2") (pinfunction "2_2") (pintype "passive"))
      (node (ref "SW3") (pin "34") (pintype "passive"))
      (node (ref "U0") (pin "20") (pinfunction "VDD3P3_RTC_20") (pintype "power_in"))
      (node (ref "U0") (pin "29") (pinfunction "VDD_SPI_29") (pintype "power_in"))
      (node (ref "U0") (pin "46") (pinfunction "VDD3P3_CPU_46") (pintype "power_in"))
      (node (ref "U0") (pin "55") (pinfunction "VDDA1_55") (pintype "power_in"))
      (node (ref "U0") (pin "56") (pinfunction "VDDA2_56") (pintype "power_in"))
      (node (ref "U10") (pin "8") (pinfunction "VCC_8") (pintype "power_in"))
      (node (ref "U3") (pin "8") (pinfunction "VCC_8") (pintype "power_in"))
      (node (ref "U6") (pin "5") (pinfunction "VOUT_5") (pintype "power_in"))
    )
    (net (code "39") (name "unconnected-(J1-SBU1-PadA8)") (class "Default")
      (node (ref "J1") (pin "A8") (pinfunction "SBU1_A8") (pintype "passive+no_connect"))
    )
    (net (code "40") (name "unconnected-(J1-SBU2-PadB8)") (class "Default")
      (node (ref "J1") (pin "B8") (pinfunction "SBU2_B8") (pintype "passive+no_connect"))
    )
    (net (code "41") (name "unconnected-(J1-SHIELD-PadSH)") (class "Default")
      (node (ref "J1") (pin "SH") (pinfunction "SHIELD_SH") (pintype "passive+no_connect"))
    )
    (net (code "42") (name "unconnected-(U0-GPIO1-Pad6)") (class "Default")
      (node (ref "U0") (pin "6") (pinfunction "GPIO1_6") (pintype "bidirectional+no_connect"))
    )
    (net (code "43") (name "unconnected-(U0-GPIO2-Pad7)") (class "Default")
      (node (ref "U0") (pin "7") (pinfunction "GPIO2_7") (pintype "bidirectional+no_connect"))
    )
    (net (code "44") (name "unconnected-(U0-GPIO3-Pad8)") (class "Default")
      (node (ref "U0") (pin "8") (pinfunction "GPIO3_8") (pintype "bidirectional+no_connect"))
    )
    (net (code "45") (name "unconnected-(U0-GPIO4-Pad9)") (class "Default")
      (node (ref "U0") (pin "9") (pinfunction "GPIO4_9") (pintype "bidirectional+no_connect"))
    )
    (net (code "46") (name "unconnected-(U0-GPIO5-Pad10)") (class "Default")
      (node (ref "U0") (pin "10") (pinfunction "GPIO5_10") (pintype "bidirectional+no_connect"))
    )
    (net (code "47") (name "unconnected-(U0-GPIO6-Pad11)") (class "Default")
      (node (ref "U0") (pin "11") (pinfunction "GPIO6_11") (pintype "bidirectional+no_connect"))
    )
    (net (code "48") (name "unconnected-(U0-GPIO7-Pad12)") (class "Default")
      (node (ref "U0") (pin "12") (pinfunction "GPIO7_12") (pintype "bidirectional+no_connect"))
    )
    (net (code "49") (name "unconnected-(U0-GPIO8-Pad13)") (class "Default")
      (node (ref "U0") (pin "13") (pinfunction "GPIO8_13") (pintype "bidirectional+no_connect"))
    )
    (net (code "50") (name "unconnected-(U0-GPIO9-Pad14)") (class "Default")
      (node (ref "U0") (pin "14") (pinfunction "GPIO9_14") (pintype "bidirectional+no_connect"))
    )
    (net (code "51") (name "unconnected-(U0-GPIO10-Pad15)") (class "Default")
      (node (ref "U0") (pin "15") (pinfunction "GPIO10_15") (pintype "bidirectional+no_connect"))
    )
    (net (code "52") (name "unconnected-(U0-GPIO11-Pad16)") (class "Default")
      (node (ref "U0") (pin "16") (pinfunction "GPIO11_16") (pintype "bidirectional+no_connect"))
    )
    (net (code "53") (name "unconnected-(U0-GPIO12-Pad17)") (class "Default")
      (node (ref "U0") (pin "17") (pinfunction "GPIO12_17") (pintype "bidirectional+no_connect"))
    )
    (net (code "54") (name "unconnected-(U0-GPIO13-Pad18)") (class "Default")
      (node (ref "U0") (pin "18") (pinfunction "GPIO13_18") (pintype "bidirectional+no_connect"))
    )
    (net (code "55") (name "unconnected-(U0-GPIO14-Pad19)") (class "Default")
      (node (ref "U0") (pin "19") (pinfunction "GPIO14_19") (pintype "bidirectional+no_connect"))
    )
    (net (code "56") (name "unconnected-(U0-GPIO17-Pad23)") (class "Default")
      (node (ref "U0") (pin "23") (pinfunction "GPIO17_23") (pintype "bidirectional+no_connect"))
    )
    (net (code "57") (name "unconnected-(U0-GPIO21-Pad27)") (class "Default")
      (node (ref "U0") (pin "27") (pinfunction "GPIO21_27") (pintype "bidirectional+no_connect"))
    )
    (net (code "58") (name "unconnected-(U0-GPIO33-Pad38)") (class "Default")
      (node (ref "U0") (pin "38") (pinfunction "GPIO33_38") (pintype "bidirectional+no_connect"))
    )
    (net (code "59") (name "unconnected-(U0-GPIO34-Pad39)") (class "Default")
      (node (ref "U0") (pin "39") (pinfunction "GPIO34_39") (pintype "bidirectional+no_connect"))
    )
    (net (code "60") (name "unconnected-(U0-GPIO35-Pad40)") (class "Default")
      (node (ref "U0") (pin "40") (pinfunction "GPIO35_40") (pintype "bidirectional+no_connect"))
    )
    (net (code "61") (name "unconnected-(U0-GPIO36-Pad41)") (class "Default")
      (node (ref "U0") (pin "41") (pinfunction "GPIO36_41") (pintype "bidirectional+no_connect"))
    )
    (net (code "62") (name "unconnected-(U0-GPIO37-Pad42)") (class "Default")
      (node (ref "U0") (pin "42") (pinfunction "GPIO37_42") (pintype "bidirectional+no_connect"))
    )
    (net (code "63") (name "unconnected-(U0-GPIO38-Pad43)") (class "Default")
      (node (ref "U0") (pin "43") (pinfunction "GPIO38_43") (pintype "bidirectional+no_connect"))
    )
    (net (code "64") (name "unconnected-(U0-GPIO45-Pad51)") (class "Default")
      (node (ref "U0") (pin "51") (pinfunction "GPIO45_51") (pintype "bidirectional+no_connect"))
    )
    (net (code "65") (name "unconnected-(U0-MTCK-Pad44)") (class "Default")
      (node (ref "U0") (pin "44") (pinfunction "MTCK_44") (pintype "bidirectional+no_connect"))
    )
    (net (code "66") (name "unconnected-(U0-MTDI-Pad47)") (class "Default")
      (node (ref "U0") (pin "47") (pinfunction "MTDI_47") (pintype "bidirectional+no_connect"))
    )
    (net (code "67") (name "unconnected-(U0-MTDO-Pad45)") (class "Default")
      (node (ref "U0") (pin "45") (pinfunction "MTDO_45") (pintype "bidirectional+no_connect"))
    )
    (net (code "68") (name "unconnected-(U0-MTMS-Pad48)") (class "Default")
      (node (ref "U0") (pin "48") (pinfunction "MTMS_48") (pintype "bidirectional+no_connect"))
    )
    (net (code "69") (name "unconnected-(U0-SPICLK_N-Pad36)") (class "Default")
      (node (ref "U0") (pin "36") (pinfunction "SPICLK_N_36") (pintype "bidirectional+no_connect"))
    )
    (net (code "70") (name "unconnected-(U0-SPICLK_P-Pad37)") (class "Default")
      (node (ref "U0") (pin "37") (pinfunction "SPICLK_P_37") (pintype "bidirectional+no_connect"))
    )
    (net (code "71") (name "unconnected-(U0-U0RXD-Pad50)") (class "Default")
      (node (ref "U0") (pin "50") (pinfunction "U0RXD_50") (pintype "bidirectional+no_connect"))
    )
    (net (code "72") (name "unconnected-(U0-U0TXD-Pad49)") (class "Default")
      (node (ref "U0") (pin "49") (pinfunction "U0TXD_49") (pintype "bidirectional+no_connect"))
    )
    (net (code "73") (name "unconnected-(U4--VOUT-Pad4)") (class "Default")
      (node (ref "U4") (pin "4") (pinfunction "-VOUT_4") (pintype "passive+no_connect"))
    )
    (net (code "74") (name "unconnected-(U5-VBUS_SYS-PadA2)") (class "Default")
      (node (ref "U5") (pin "A2") (pinfunction "VBUS_SYS_A2") (pintype "power_in+no_connect"))
    )
    (net (code "75") (name "unconnected-(U5-VBUS_SYS-PadA3)") (class "Default")
      (node (ref "U5") (pin "A3") (pinfunction "VBUS_SYS_A3") (pintype "power_in+no_connect"))
    )
    (net (code "76") (name "unconnected-(U5-VBUS_SYS-PadB2)") (class "Default")
      (node (ref "U5") (pin "B2") (pinfunction "VBUS_SYS_B2") (pintype "power_in+no_connect"))
    )
    (net (code "77") (name "unconnected-(U7-IO4-Pad4)") (class "Default")
      (node (ref "U7") (pin "4") (pinfunction "IO4_4") (pintype "bidirectional+no_connect"))
    )
  )
)
